# door-sensor.net
KiCad netlist of a schematic drawn in EAGLE
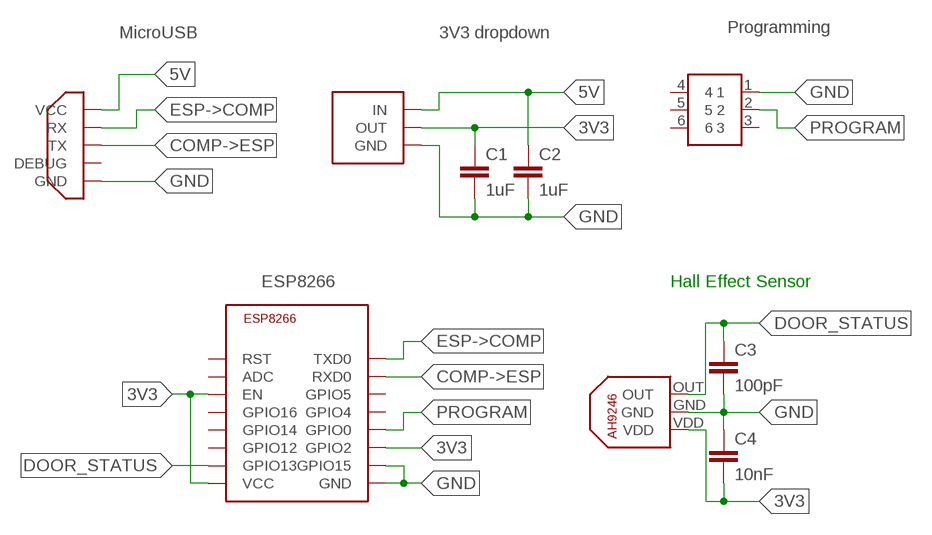
[diagram p0: schematic, sheet 1]

(export (version "E")
  (design (tool "Eeschema 10.0.6"))
  (components
    (comp (ref "C1")
      (value "1uF")
      (footprint "eagle-import:C0805")
      (libsource (lib "eagle-import") (part "C-EUC0805"))
    )
    (comp (ref "C2")
      (value "1uF")
      (footprint "eagle-import:C0805")
      (libsource (lib "eagle-import") (part "C-EUC0805"))
    )
    (comp (ref "C3")
      (value "100pF")
      (footprint "eagle-import:C0805")
      (libsource (lib "eagle-import") (part "C-EUC0805"))
    )
    (comp (ref "C4")
      (value "10nF")
      (footprint "eagle-import:C0805")
      (libsource (lib "eagle-import") (part "C-EUC0805"))
    )
    (comp (ref "U$2")
      (value "MICROUSB609-4613-1-ND")
      (footprint "eagle-import:MICROUSB")
      (libsource (lib "eagle-import") (part "MICROUSB609-4613-1-ND"))
    )
    (comp (ref "U$4")
      (value "AZ1117E")
      (footprint "eagle-import:SOT-223")
      (libsource (lib "eagle-import") (part "AZ1117E"))
    )
    (comp (ref "U$6")
      (value "ESP8266-12E-SMD")
      (footprint "eagle-import:ESP8266-12E-SMD")
      (libsource (lib "eagle-import") (part "ESP8266-12E-SMD"))
    )
    (comp (ref "U$7")
      (value "AYZ0202AGRL")
      (footprint "eagle-import:AYZ0202AGRL")
      (libsource (lib "eagle-import") (part "AYZ0202AGRL"))
    )
    (comp (ref "U$8")
      (value "AH9246SC59")
      (footprint "eagle-import:SC59")
      (libsource (lib "eagle-import") (part "AH9246SC59"))
    )
  )
  (nets
    (net (code "1") (name "3V3") (class "Default")
      (node (ref "C1") (pin "1") (pinfunction "1_1") (pintype "passive"))
      (node (ref "C4") (pin "2") (pinfunction "2_2") (pintype "passive"))
      (node (ref "U$4") (pin "P$1") (pinfunction "OUT_P$1") (pintype "output"))
      (node (ref "U$4") (pin "P$2") (pinfunction "OUT_P$2") (pintype "output"))
      (node (ref "U$6") (pin "EN") (pinfunction "EN_EN") (pintype "input"))
      (node (ref "U$6") (pin "GPIO2") (pinfunction "GPIO2_GPIO2") (pintype "bidirectional"))
      (node (ref "U$6") (pin "VCC") (pinfunction "VCC_VCC") (pintype "power_in"))
      (node (ref "U$8") (pin "VDD") (pinfunction "VDD_VDD") (pintype "power_in"))
    )
    (net (code "2") (name "5V") (class "Default")
      (node (ref "C2") (pin "1") (pinfunction "1_1") (pintype "passive"))
      (node (ref "U$2") (pin "VCC") (pinfunction "VCC_VCC") (pintype "power_in"))
      (node (ref "U$4") (pin "P$4") (pinfunction "IN_P$4") (pintype "input"))
    )
    (net (code "3") (name "COMP->ESP") (class "Default")
      (node (ref "U$2") (pin "TX") (pinfunction "TX_TX") (pintype "bidirectional"))
      (node (ref "U$6") (pin "RXD0") (pinfunction "RXD0_RXD0") (pintype "bidirectional"))
    )
    (net (code "4") (name "DOOR_STATUS") (class "Default")
      (node (ref "C3") (pin "1") (pinfunction "1_1") (pintype "passive"))
      (node (ref "U$6") (pin "GPIO13") (pinfunction "GPIO13_GPIO13") (pintype "bidirectional"))
      (node (ref "U$8") (pin "OUT") (pinfunction "OUT_OUT") (pintype "output"))
    )
    (net (code "5") (name "ESP->COMP") (class "Default")
      (node (ref "U$2") (pin "RX") (pinfunction "RX_RX") (pintype "bidirectional"))
      (node (ref "U$6") (pin "TXD0") (pinfunction "TXD0_TXD0") (pintype "bidirectional"))
    )
    (net (code "6") (name "GND") (class "Default")
      (node (ref "C1") (pin "2") (pinfunction "2_2") (pintype "passive"))
      (node (ref "C2") (pin "2") (pinfunction "2_2") (pintype "passive"))
      (node (ref "C3") (pin "2") (pinfunction "2_2") (pintype "passive"))
      (node (ref "C4") (pin "1") (pinfunction "1_1") (pintype "passive"))
      (node (ref "U$2") (pin "GND") (pinfunction "GND_GND") (pintype "power_in"))
      (node (ref "U$4") (pin "P$3") (pinfunction "GND_P$3") (pintype "power_in"))
      (node (ref "U$6") (pin "GND") (pinfunction "GND_GND") (pintype "power_in"))
      (node (ref "U$6") (pin "GPIO15") (pinfunction "GPIO15_GPIO15") (pintype "bidirectional"))
      (node (ref "U$7") (pin "1") (pinfunction "1_1") (pintype "bidirectional"))
      (node (ref "U$8") (pin "GND") (pinfunction "GND_GND") (pintype "power_in"))
    )
    (net (code "7") (name "PROGRAM") (class "Default")
      (node (ref "U$6") (pin "GPIO0") (pinfunction "GPIO0_GPIO0") (pintype "bidirectional"))
      (node (ref "U$7") (pin "2") (pinfunction "2_2") (pintype "bidirectional"))
    )
    (net (code "8") (name "unconnected-(U$2-PadDEBUG)") (class "Default")
      (node (ref "U$2") (pin "DEBUG") (pinfunction "DEBUG_DEBUG") (pintype "bidirectional"))
    )
    (net (code "9") (name "unconnected-(U$6-PadADC)") (class "Default")
      (node (ref "U$6") (pin "ADC") (pinfunction "ADC_ADC") (pintype "input"))
    )
    (net (code "10") (name "unconnected-(U$6-PadGPIO4)") (class "Default")
      (node (ref "U$6") (pin "GPIO4") (pinfunction "GPIO4_GPIO4") (pintype "bidirectional"))
    )
    (net (code "11") (name "unconnected-(U$6-PadGPIO5)") (class "Default")
      (node (ref "U$6") (pin "GPIO5") (pinfunction "GPIO5_GPIO5") (pintype "bidirectional"))
    )
    (net (code "12") (name "unconnected-(U$6-PadGPIO12)") (class "Default")
      (node (ref "U$6") (pin "GPIO12") (pinfunction "GPIO12_GPIO12") (pintype "bidirectional"))
    )
    (net (code "13") (name "unconnected-(U$6-PadGPIO14)") (class "Default")
      (node (ref "U$6") (pin "GPIO14") (pinfunction "GPIO14_GPIO14") (pintype "bidirectional"))
    )
    (net (code "14") (name "unconnected-(U$6-PadGPIO16)") (class "Default")
      (node (ref "U$6") (pin "GPIO16") (pinfunction "GPIO16_GPIO16") (pintype "bidirectional"))
    )
    (net (code "15") (name "unconnected-(U$6-PadRST)") (class "Default")
      (node (ref "U$6") (pin "RST") (pinfunction "RST_RST") (pintype "input"))
    )
    (net (code "16") (name "unconnected-(U$7-Pad3)") (class "Default")
      (node (ref "U$7") (pin "3") (pinfunction "3_3") (pintype "bidirectional"))
    )
    (net (code "17") (name "unconnected-(U$7-Pad4)") (class "Default")
      (node (ref "U$7") (pin "4") (pinfunction "4_4") (pintype "bidirectional"))
    )
    (net (code "18") (name "unconnected-(U$7-Pad5)") (class "Default")
      (node (ref "U$7") (pin "5") (pinfunction "5_5") (pintype "bidirectional"))
    )
    (net (code "19") (name "unconnected-(U$7-Pad6)") (class "Default")
      (node (ref "U$7") (pin "6") (pinfunction "6_6") (pintype "bidirectional"))
    )
  )
)
